# attenumixer.net
KiCad netlist of a schematic drawn in EAGLE
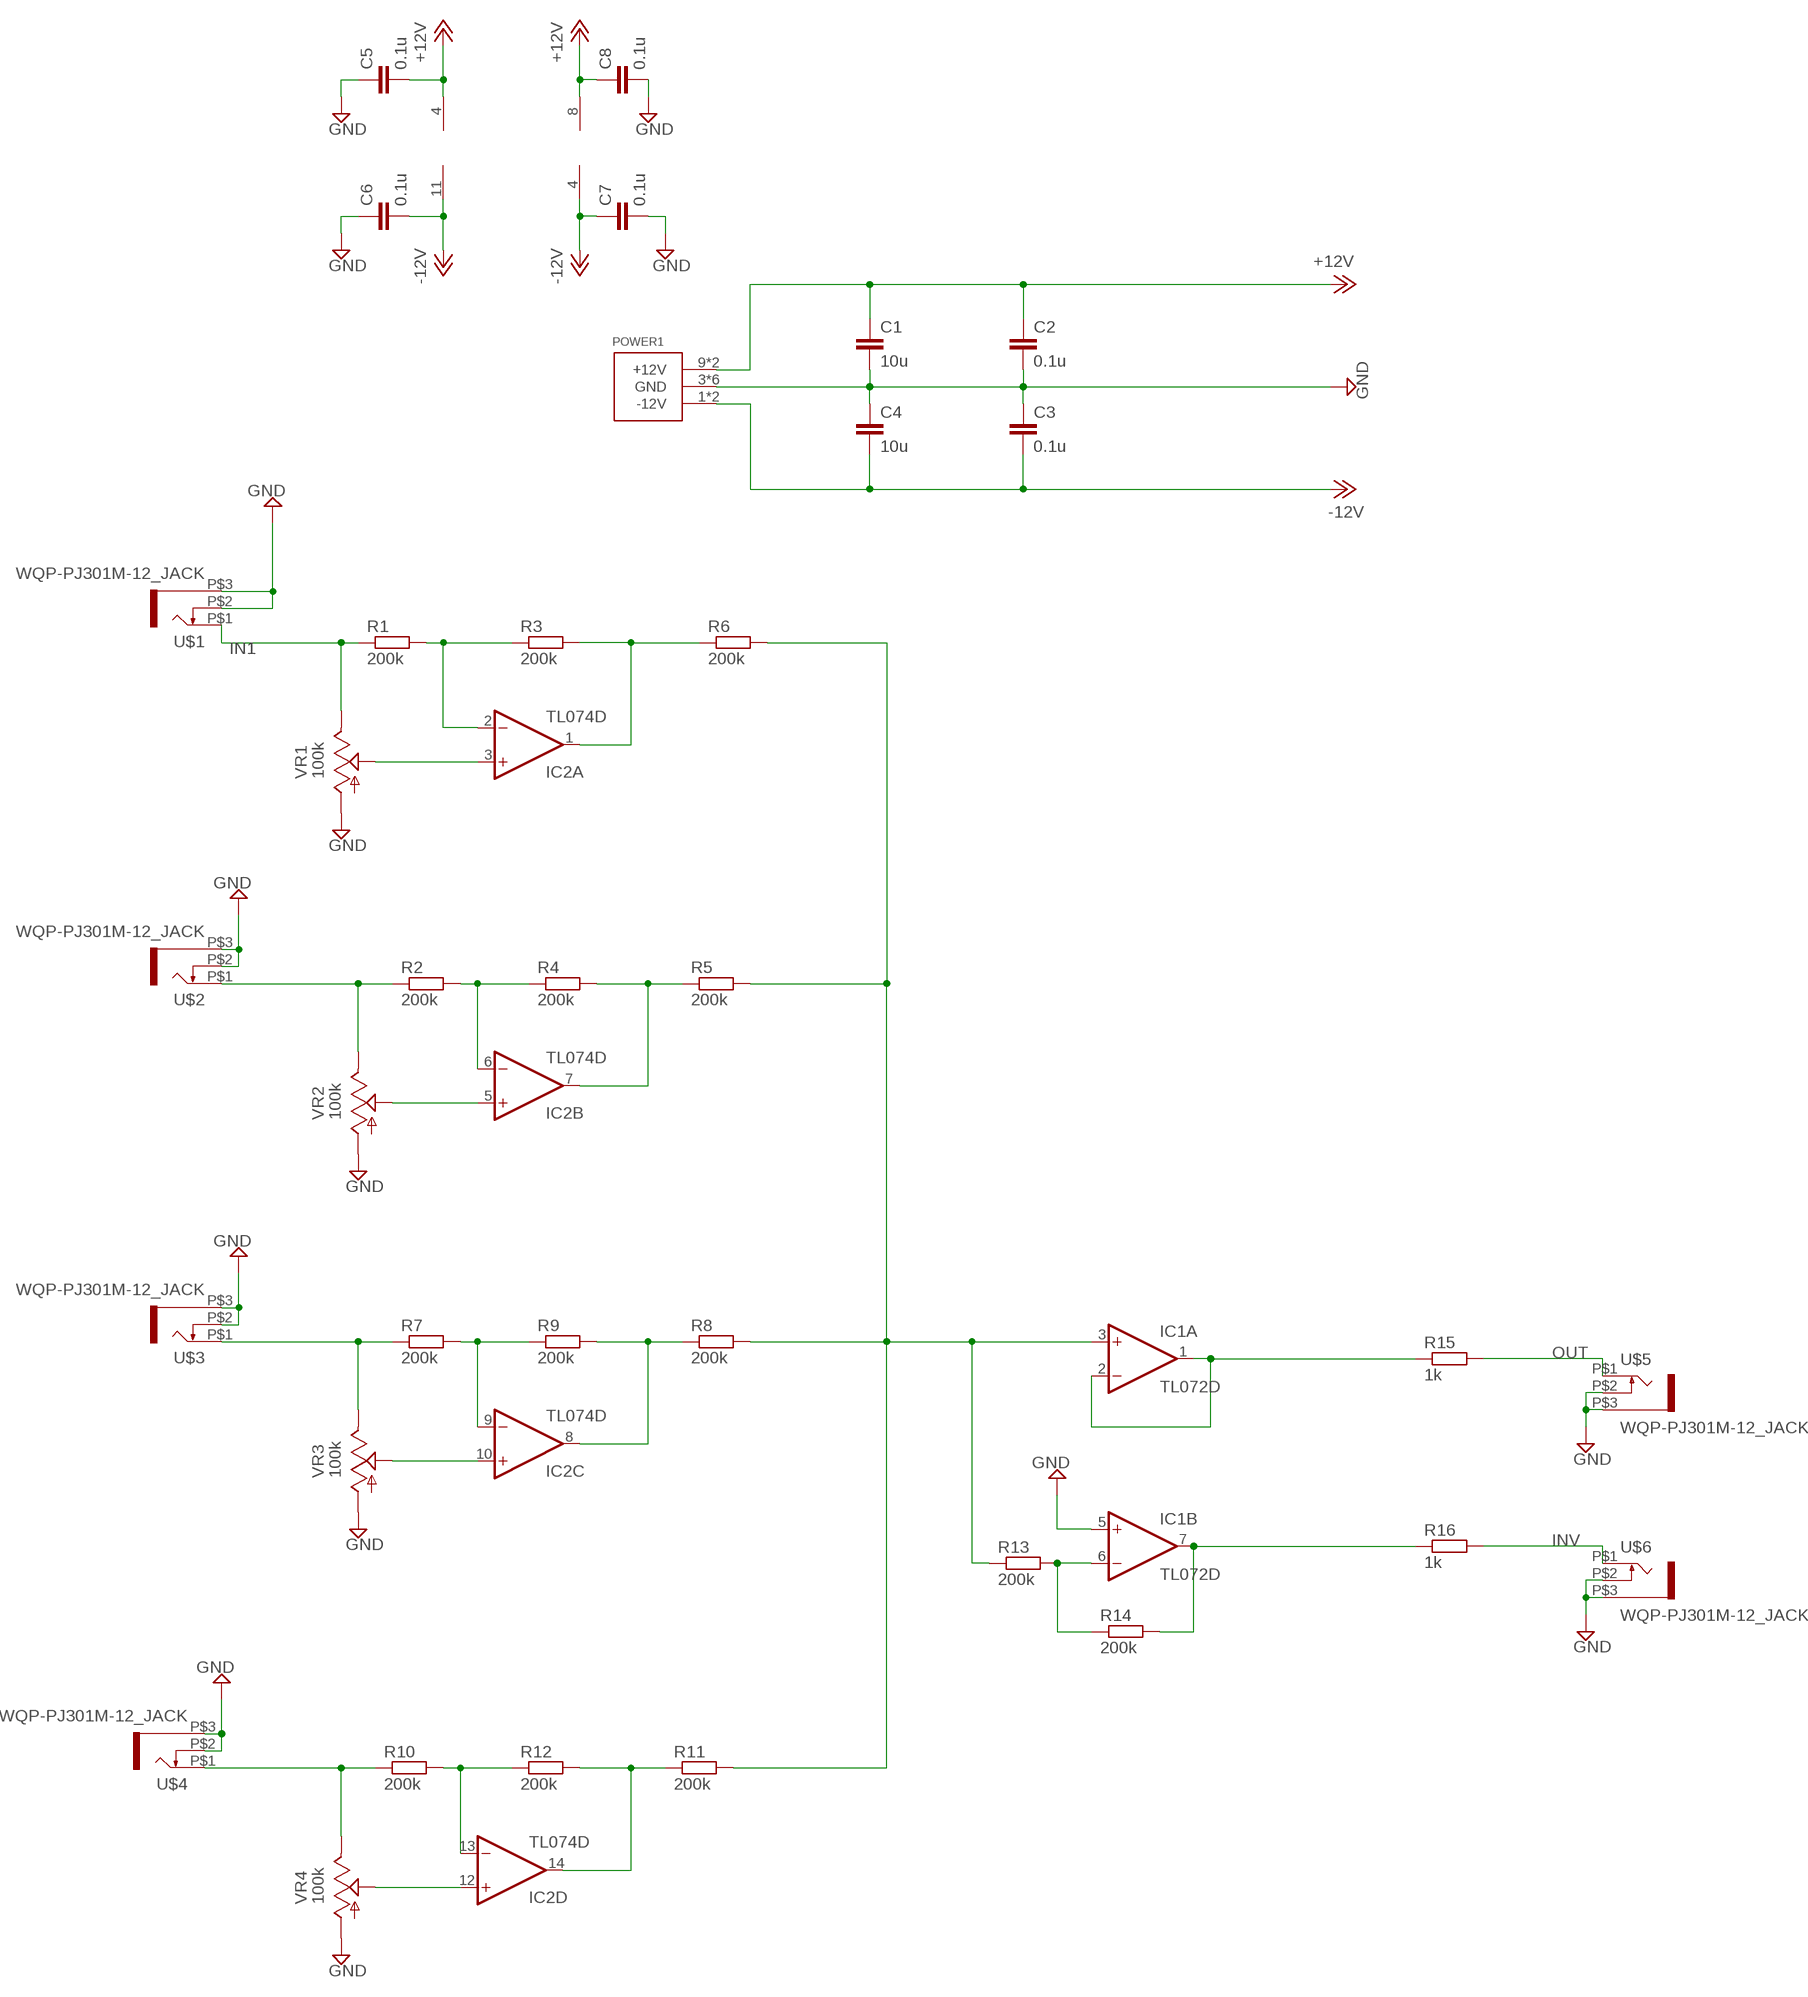
[diagram p0: schematic, sheet 1]

(export (version "E")
  (design (tool "Eeschema 10.0.6"))
  (components
    (comp (ref "C1")
      (value "10u")
      (footprint "eagle-import:C0805")
      (libsource (lib "eagle-import") (part "C-EUC0805"))
    )
    (comp (ref "C2")
      (value "0.1u")
      (footprint "eagle-import:C0805")
      (libsource (lib "eagle-import") (part "C-EUC0805"))
    )
    (comp (ref "C3")
      (value "0.1u")
      (footprint "eagle-import:C0805")
      (libsource (lib "eagle-import") (part "C-EUC0805"))
    )
    (comp (ref "C4")
      (value "10u")
      (footprint "eagle-import:C0805")
      (libsource (lib "eagle-import") (part "C-EUC0805"))
    )
    (comp (ref "C5")
      (value "0.1u")
      (footprint "eagle-import:C0805")
      (libsource (lib "eagle-import") (part "C-EUC0805"))
    )
    (comp (ref "C6")
      (value "0.1u")
      (footprint "eagle-import:C0805")
      (libsource (lib "eagle-import") (part "C-EUC0805"))
    )
    (comp (ref "C7")
      (value "0.1u")
      (footprint "eagle-import:C0805")
      (libsource (lib "eagle-import") (part "C-EUC0805"))
    )
    (comp (ref "C8")
      (value "0.1u")
      (footprint "eagle-import:C0805")
      (libsource (lib "eagle-import") (part "C-EUC0805"))
    )
    (comp (ref "IC1")
      (value "TL072D")
      (footprint "eagle-import:SO08")
      (libsource (lib "eagle-import") (part "TL072D"))
    )
    (comp (ref "IC2")
      (value "TL074D")
      (footprint "eagle-import:SO14")
      (libsource (lib "eagle-import") (part "TL074D"))
    )
    (comp (ref "POWER1")
      (value "POWER_SIMPLE10")
      (footprint "eagle-import:POWER_10")
      (libsource (lib "eagle-import") (part "POWER_SIMPLE10"))
    )
    (comp (ref "R1")
      (value "200k")
      (footprint "eagle-import:R0805")
      (libsource (lib "eagle-import") (part "R-EU_R0805"))
    )
    (comp (ref "R2")
      (value "200k")
      (footprint "eagle-import:R0805")
      (libsource (lib "eagle-import") (part "R-EU_R0805"))
    )
    (comp (ref "R3")
      (value "200k")
      (footprint "eagle-import:R0805")
      (libsource (lib "eagle-import") (part "R-EU_R0805"))
    )
    (comp (ref "R4")
      (value "200k")
      (footprint "eagle-import:R0805")
      (libsource (lib "eagle-import") (part "R-EU_R0805"))
    )
    (comp (ref "R5")
      (value "200k")
      (footprint "eagle-import:R0805")
      (libsource (lib "eagle-import") (part "R-EU_R0805"))
    )
    (comp (ref "R6")
      (value "200k")
      (footprint "eagle-import:R0805")
      (libsource (lib "eagle-import") (part "R-EU_R0805"))
    )
    (comp (ref "R7")
      (value "200k")
      (footprint "eagle-import:R0805")
      (libsource (lib "eagle-import") (part "R-EU_R0805"))
    )
    (comp (ref "R8")
      (value "200k")
      (footprint "eagle-import:R0805")
      (libsource (lib "eagle-import") (part "R-EU_R0805"))
    )
    (comp (ref "R9")
      (value "200k")
      (footprint "eagle-import:R0805")
      (libsource (lib "eagle-import") (part "R-EU_R0805"))
    )
    (comp (ref "R10")
      (value "200k")
      (footprint "eagle-import:R0805")
      (libsource (lib "eagle-import") (part "R-EU_R0805"))
    )
    (comp (ref "R11")
      (value "200k")
      (footprint "eagle-import:R0805")
      (libsource (lib "eagle-import") (part "R-EU_R0805"))
    )
    (comp (ref "R12")
      (value "200k")
      (footprint "eagle-import:R0805")
      (libsource (lib "eagle-import") (part "R-EU_R0805"))
    )
    (comp (ref "R13")
      (value "200k")
      (footprint "eagle-import:R0805")
      (libsource (lib "eagle-import") (part "R-EU_R0805"))
    )
    (comp (ref "R14")
      (value "200k")
      (footprint "eagle-import:R0805")
      (libsource (lib "eagle-import") (part "R-EU_R0805"))
    )
    (comp (ref "R15")
      (value "1k")
      (footprint "eagle-import:R0805")
      (libsource (lib "eagle-import") (part "R-EU_R0805"))
    )
    (comp (ref "R16")
      (value "1k")
      (footprint "eagle-import:R0805")
      (libsource (lib "eagle-import") (part "R-EU_R0805"))
    )
    (comp (ref "U$1")
      (value "WQP-PJ301M-12_JACK")
      (footprint "eagle-import:WQP-PJ301M-12_JACK")
      (libsource (lib "eagle-import") (part "WQP-PJ301M-12_JACK"))
    )
    (comp (ref "U$2")
      (value "WQP-PJ301M-12_JACK")
      (footprint "eagle-import:WQP-PJ301M-12_JACK")
      (libsource (lib "eagle-import") (part "WQP-PJ301M-12_JACK"))
    )
    (comp (ref "U$3")
      (value "WQP-PJ301M-12_JACK")
      (footprint "eagle-import:WQP-PJ301M-12_JACK")
      (libsource (lib "eagle-import") (part "WQP-PJ301M-12_JACK"))
    )
    (comp (ref "U$4")
      (value "WQP-PJ301M-12_JACK")
      (footprint "eagle-import:WQP-PJ301M-12_JACK")
      (libsource (lib "eagle-import") (part "WQP-PJ301M-12_JACK"))
    )
    (comp (ref "U$5")
      (value "WQP-PJ301M-12_JACK")
      (footprint "eagle-import:WQP-PJ301M-12_JACK")
      (libsource (lib "eagle-import") (part "WQP-PJ301M-12_JACK"))
    )
    (comp (ref "U$6")
      (value "WQP-PJ301M-12_JACK")
      (footprint "eagle-import:WQP-PJ301M-12_JACK")
      (libsource (lib "eagle-import") (part "WQP-PJ301M-12_JACK"))
    )
    (comp (ref "VR1")
      (value "100k")
      (footprint "eagle-import:9MM_SNAP-IN_POT")
      (libsource (lib "eagle-import") (part "9MM_SNAP-IN_POT_"))
    )
    (comp (ref "VR2")
      (value "100k")
      (footprint "eagle-import:9MM_SNAP-IN_POT")
      (libsource (lib "eagle-import") (part "9MM_SNAP-IN_POT_"))
    )
    (comp (ref "VR3")
      (value "100k")
      (footprint "eagle-import:9MM_SNAP-IN_POT")
      (libsource (lib "eagle-import") (part "9MM_SNAP-IN_POT_"))
    )
    (comp (ref "VR4")
      (value "100k")
      (footprint "eagle-import:9MM_SNAP-IN_POT")
      (libsource (lib "eagle-import") (part "9MM_SNAP-IN_POT_"))
    )
  )
  (nets
    (net (code "1") (name "+12V") (class "Default")
      (node (ref "C1") (pin "1") (pinfunction "1_1") (pintype "passive"))
      (node (ref "C2") (pin "1") (pinfunction "1_1") (pintype "passive"))
      (node (ref "C5") (pin "2") (pinfunction "2_2") (pintype "passive"))
      (node (ref "C8") (pin "1") (pinfunction "1_1") (pintype "passive"))
      (node (ref "IC1") (pin "8") (pinfunction "V+_8") (pintype "power_in"))
      (node (ref "IC2") (pin "4") (pinfunction "V+_4") (pintype "power_in"))
      (node (ref "POWER1") (pin "10") (pinfunction "+12V_10") (pintype "bidirectional"))
      (node (ref "POWER1") (pin "9") (pinfunction "+12V_9") (pintype "bidirectional"))
    )
    (net (code "2") (name "-12V") (class "Default")
      (node (ref "C3") (pin "2") (pinfunction "2_2") (pintype "passive"))
      (node (ref "C4") (pin "2") (pinfunction "2_2") (pintype "passive"))
      (node (ref "C6") (pin "2") (pinfunction "2_2") (pintype "passive"))
      (node (ref "C7") (pin "1") (pinfunction "1_1") (pintype "passive"))
      (node (ref "IC1") (pin "4") (pinfunction "V-_4") (pintype "power_in"))
      (node (ref "IC2") (pin "11") (pinfunction "V-_11") (pintype "power_in"))
      (node (ref "POWER1") (pin "1") (pinfunction "-12V_1") (pintype "bidirectional"))
      (node (ref "POWER1") (pin "2") (pinfunction "-12V_2") (pintype "bidirectional"))
    )
    (net (code "3") (name "/IN1") (class "Default")
      (node (ref "R1") (pin "1") (pinfunction "1_1") (pintype "passive"))
      (node (ref "U$1") (pin "P$1") (pinfunction "2_P$1") (pintype "passive"))
      (node (ref "VR1") (pin "3") (pinfunction "E_3") (pintype "passive"))
    )
    (net (code "4") (name "/INV") (class "Default")
      (node (ref "R16") (pin "2") (pinfunction "2_2") (pintype "passive"))
      (node (ref "U$6") (pin "P$1") (pinfunction "2_P$1") (pintype "passive"))
    )
    (net (code "5") (name "/OUT") (class "Default")
      (node (ref "R15") (pin "2") (pinfunction "2_2") (pintype "passive"))
      (node (ref "U$5") (pin "P$1") (pinfunction "2_P$1") (pintype "passive"))
    )
    (net (code "6") (name "GND") (class "Default")
      (node (ref "C1") (pin "2") (pinfunction "2_2") (pintype "passive"))
      (node (ref "C2") (pin "2") (pinfunction "2_2") (pintype "passive"))
      (node (ref "C3") (pin "1") (pinfunction "1_1") (pintype "passive"))
      (node (ref "C4") (pin "1") (pinfunction "1_1") (pintype "passive"))
      (node (ref "C5") (pin "1") (pinfunction "1_1") (pintype "passive"))
      (node (ref "C6") (pin "1") (pinfunction "1_1") (pintype "passive"))
      (node (ref "C7") (pin "2") (pinfunction "2_2") (pintype "passive"))
      (node (ref "C8") (pin "2") (pinfunction "2_2") (pintype "passive"))
      (node (ref "IC1") (pin "5") (pinfunction "+IN_5") (pintype "input"))
      (node (ref "POWER1") (pin "3") (pinfunction "GND_3") (pintype "bidirectional"))
      (node (ref "POWER1") (pin "4") (pinfunction "GND_4") (pintype "bidirectional"))
      (node (ref "POWER1") (pin "5") (pinfunction "GND_5") (pintype "bidirectional"))
      (node (ref "POWER1") (pin "6") (pinfunction "GND_6") (pintype "bidirectional"))
      (node (ref "POWER1") (pin "7") (pinfunction "GND_7") (pintype "bidirectional"))
      (node (ref "POWER1") (pin "8") (pinfunction "GND_8") (pintype "bidirectional"))
      (node (ref "U$1") (pin "P$2") (pinfunction "3_P$2") (pintype "passive"))
      (node (ref "U$1") (pin "P$3") (pinfunction "1_P$3") (pintype "passive"))
      (node (ref "U$2") (pin "P$2") (pinfunction "3_P$2") (pintype "passive"))
      (node (ref "U$2") (pin "P$3") (pinfunction "1_P$3") (pintype "passive"))
      (node (ref "U$3") (pin "P$2") (pinfunction "3_P$2") (pintype "passive"))
      (node (ref "U$3") (pin "P$3") (pinfunction "1_P$3") (pintype "passive"))
      (node (ref "U$4") (pin "P$2") (pinfunction "3_P$2") (pintype "passive"))
      (node (ref "U$4") (pin "P$3") (pinfunction "1_P$3") (pintype "passive"))
      (node (ref "U$5") (pin "P$2") (pinfunction "3_P$2") (pintype "passive"))
      (node (ref "U$5") (pin "P$3") (pinfunction "1_P$3") (pintype "passive"))
      (node (ref "U$6") (pin "P$2") (pinfunction "3_P$2") (pintype "passive"))
      (node (ref "U$6") (pin "P$3") (pinfunction "1_P$3") (pintype "passive"))
      (node (ref "VR1") (pin "1") (pinfunction "A_1") (pintype "passive"))
      (node (ref "VR2") (pin "1") (pinfunction "A_1") (pintype "passive"))
      (node (ref "VR3") (pin "1") (pinfunction "A_1") (pintype "passive"))
      (node (ref "VR4") (pin "1") (pinfunction "A_1") (pintype "passive"))
    )
    (net (code "7") (name "Net-(IC1A-+IN)") (class "Default")
      (node (ref "IC1") (pin "3") (pinfunction "+IN_3") (pintype "input"))
      (node (ref "R11") (pin "2") (pinfunction "2_2") (pintype "passive"))
      (node (ref "R13") (pin "1") (pinfunction "1_1") (pintype "passive"))
      (node (ref "R5") (pin "2") (pinfunction "2_2") (pintype "passive"))
      (node (ref "R6") (pin "2") (pinfunction "2_2") (pintype "passive"))
      (node (ref "R8") (pin "2") (pinfunction "2_2") (pintype "passive"))
    )
    (net (code "8") (name "Net-(IC1A--IN)") (class "Default")
      (node (ref "IC1") (pin "1") (pinfunction "OUT_1") (pintype "output"))
      (node (ref "IC1") (pin "2") (pinfunction "-IN_2") (pintype "input"))
      (node (ref "R15") (pin "1") (pinfunction "1_1") (pintype "passive"))
    )
    (net (code "9") (name "Net-(IC1B--IN)") (class "Default")
      (node (ref "IC1") (pin "6") (pinfunction "-IN_6") (pintype "input"))
      (node (ref "R13") (pin "2") (pinfunction "2_2") (pintype "passive"))
      (node (ref "R14") (pin "1") (pinfunction "1_1") (pintype "passive"))
    )
    (net (code "10") (name "Net-(IC1B-OUT)") (class "Default")
      (node (ref "IC1") (pin "7") (pinfunction "OUT_7") (pintype "output"))
      (node (ref "R14") (pin "2") (pinfunction "2_2") (pintype "passive"))
      (node (ref "R16") (pin "1") (pinfunction "1_1") (pintype "passive"))
    )
    (net (code "11") (name "Net-(IC2A-+IN)") (class "Default")
      (node (ref "IC2") (pin "3") (pinfunction "+IN_3") (pintype "input"))
      (node (ref "VR1") (pin "2") (pinfunction "S_2") (pintype "passive"))
    )
    (net (code "12") (name "Net-(IC2A--IN)") (class "Default")
      (node (ref "IC2") (pin "2") (pinfunction "-IN_2") (pintype "input"))
      (node (ref "R1") (pin "2") (pinfunction "2_2") (pintype "passive"))
      (node (ref "R3") (pin "1") (pinfunction "1_1") (pintype "passive"))
    )
    (net (code "13") (name "Net-(IC2A-OUT)") (class "Default")
      (node (ref "IC2") (pin "1") (pinfunction "OUT_1") (pintype "output"))
      (node (ref "R3") (pin "2") (pinfunction "2_2") (pintype "passive"))
      (node (ref "R6") (pin "1") (pinfunction "1_1") (pintype "passive"))
    )
    (net (code "14") (name "Net-(IC2B-+IN)") (class "Default")
      (node (ref "IC2") (pin "5") (pinfunction "+IN_5") (pintype "input"))
      (node (ref "VR2") (pin "2") (pinfunction "S_2") (pintype "passive"))
    )
    (net (code "15") (name "Net-(IC2B--IN)") (class "Default")
      (node (ref "IC2") (pin "6") (pinfunction "-IN_6") (pintype "input"))
      (node (ref "R2") (pin "2") (pinfunction "2_2") (pintype "passive"))
      (node (ref "R4") (pin "1") (pinfunction "1_1") (pintype "passive"))
    )
    (net (code "16") (name "Net-(IC2B-OUT)") (class "Default")
      (node (ref "IC2") (pin "7") (pinfunction "OUT_7") (pintype "output"))
      (node (ref "R4") (pin "2") (pinfunction "2_2") (pintype "passive"))
      (node (ref "R5") (pin "1") (pinfunction "1_1") (pintype "passive"))
    )
    (net (code "17") (name "Net-(IC2C-+IN)") (class "Default")
      (node (ref "IC2") (pin "10") (pinfunction "+IN_10") (pintype "input"))
      (node (ref "VR3") (pin "2") (pinfunction "S_2") (pintype "passive"))
    )
    (net (code "18") (name "Net-(IC2C--IN)") (class "Default")
      (node (ref "IC2") (pin "9") (pinfunction "-IN_9") (pintype "input"))
      (node (ref "R7") (pin "2") (pinfunction "2_2") (pintype "passive"))
      (node (ref "R9") (pin "1") (pinfunction "1_1") (pintype "passive"))
    )
    (net (code "19") (name "Net-(IC2C-OUT)") (class "Default")
      (node (ref "IC2") (pin "8") (pinfunction "OUT_8") (pintype "output"))
      (node (ref "R8") (pin "1") (pinfunction "1_1") (pintype "passive"))
      (node (ref "R9") (pin "2") (pinfunction "2_2") (pintype "passive"))
    )
    (net (code "20") (name "Net-(IC2D-+IN)") (class "Default")
      (node (ref "IC2") (pin "12") (pinfunction "+IN_12") (pintype "input"))
      (node (ref "VR4") (pin "2") (pinfunction "S_2") (pintype "passive"))
    )
    (net (code "21") (name "Net-(IC2D--IN)") (class "Default")
      (node (ref "IC2") (pin "13") (pinfunction "-IN_13") (pintype "input"))
      (node (ref "R10") (pin "2") (pinfunction "2_2") (pintype "passive"))
      (node (ref "R12") (pin "1") (pinfunction "1_1") (pintype "passive"))
    )
    (net (code "22") (name "Net-(IC2D-OUT)") (class "Default")
      (node (ref "IC2") (pin "14") (pinfunction "OUT_14") (pintype "output"))
      (node (ref "R11") (pin "1") (pinfunction "1_1") (pintype "passive"))
      (node (ref "R12") (pin "2") (pinfunction "2_2") (pintype "passive"))
    )
    (net (code "23") (name "Net-(U$2-2)") (class "Default")
      (node (ref "R2") (pin "1") (pinfunction "1_1") (pintype "passive"))
      (node (ref "U$2") (pin "P$1") (pinfunction "2_P$1") (pintype "passive"))
      (node (ref "VR2") (pin "3") (pinfunction "E_3") (pintype "passive"))
    )
    (net (code "24") (name "Net-(U$3-2)") (class "Default")
      (node (ref "R7") (pin "1") (pinfunction "1_1") (pintype "passive"))
      (node (ref "U$3") (pin "P$1") (pinfunction "2_P$1") (pintype "passive"))
      (node (ref "VR3") (pin "3") (pinfunction "E_3") (pintype "passive"))
    )
    (net (code "25") (name "Net-(U$4-2)") (class "Default")
      (node (ref "R10") (pin "1") (pinfunction "1_1") (pintype "passive"))
      (node (ref "U$4") (pin "P$1") (pinfunction "2_P$1") (pintype "passive"))
      (node (ref "VR4") (pin "3") (pinfunction "E_3") (pintype "passive"))
    )
  )
)
